# HPI_dice.net
KiCad netlist of a schematic drawn in EAGLE
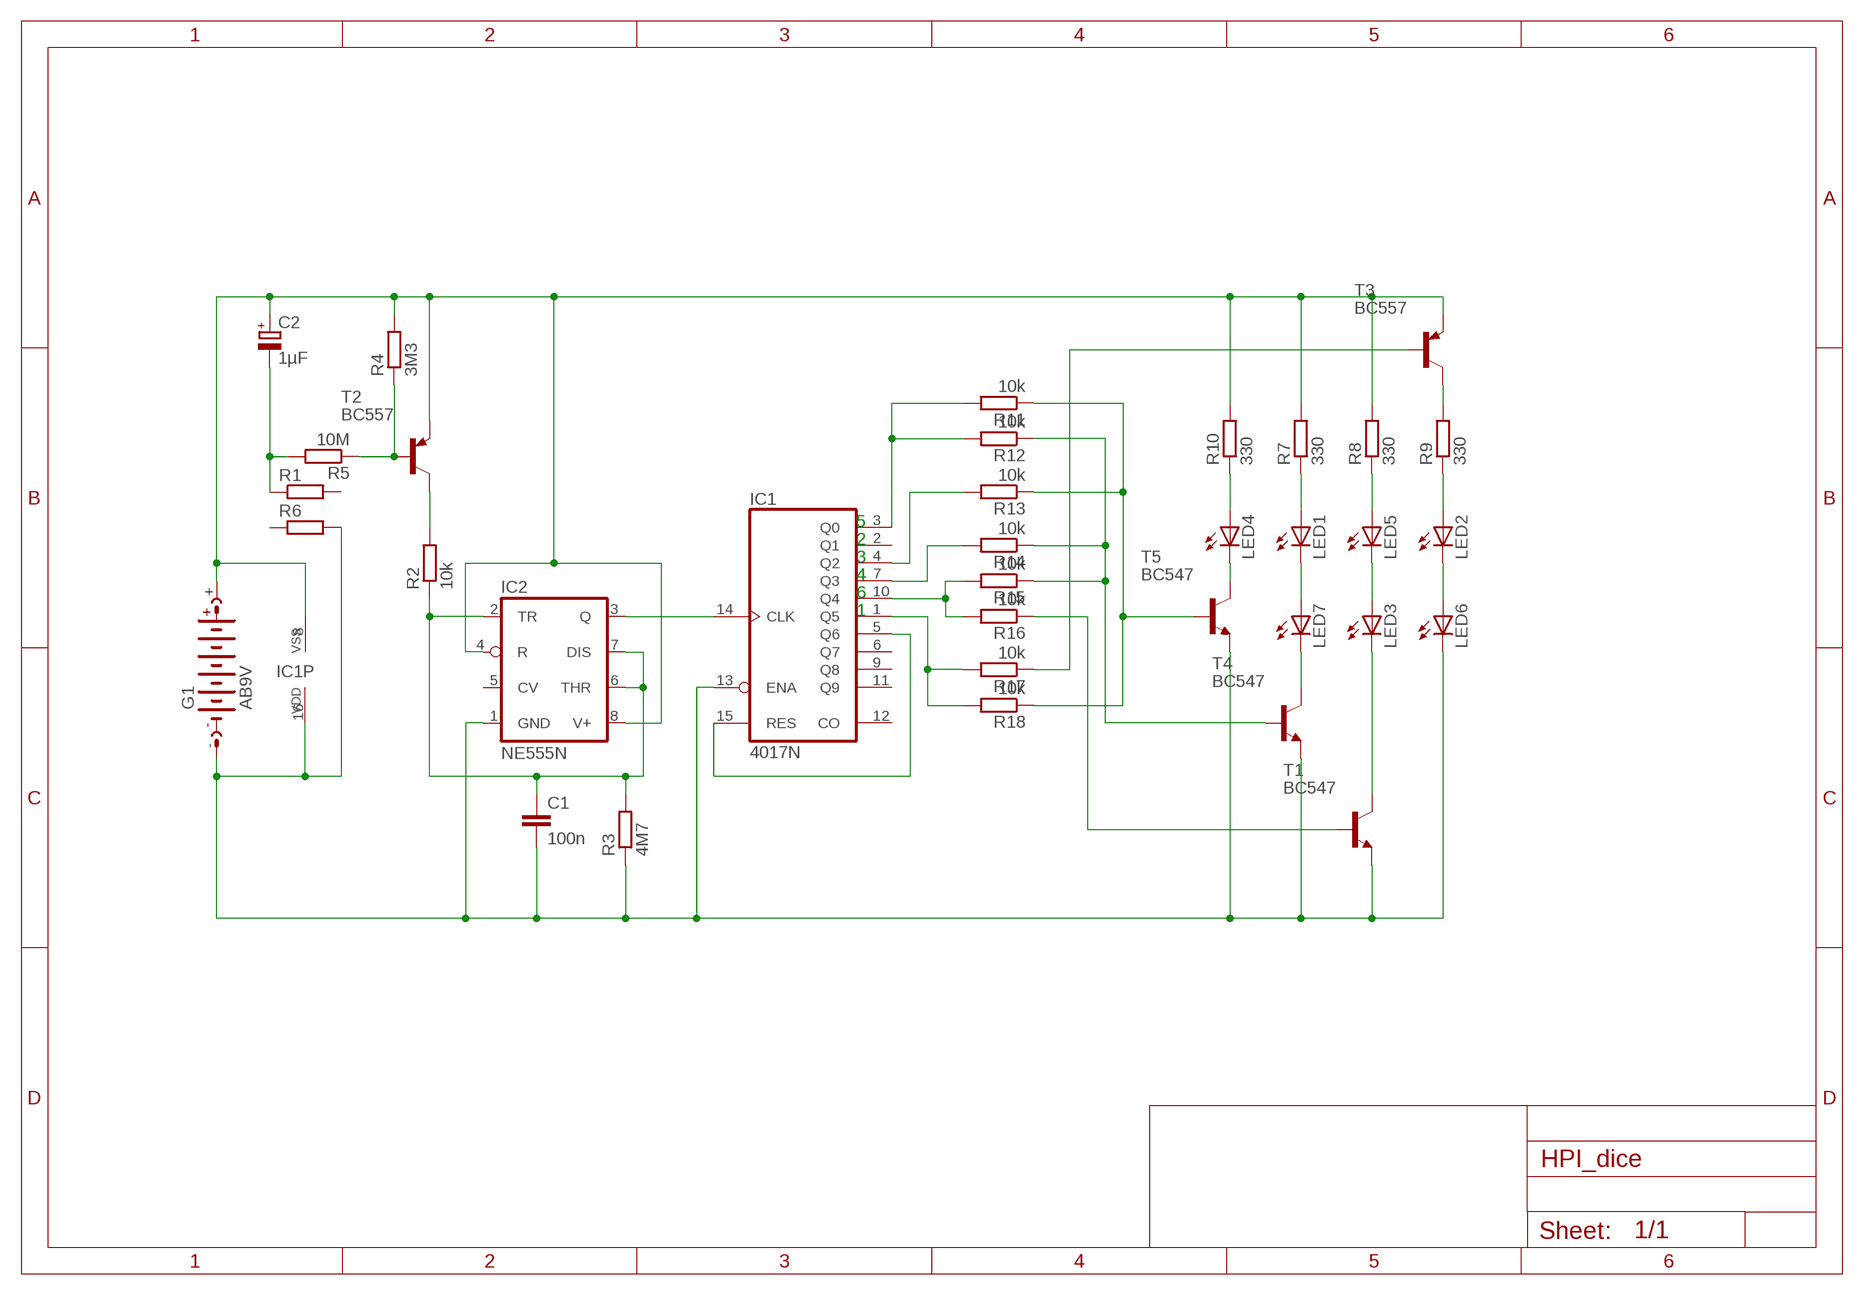
[diagram p0: schematic, sheet 1]

(export (version "E")
  (design (tool "Eeschema 10.0.6"))
  (components
    (comp (ref "C1")
      (value "100n")
      (footprint "eagle-import:C050-025X075")
      (libsource (lib "eagle-import") (part "C-EU050-025X075"))
    )
    (comp (ref "C2")
      (value "1µF")
      (footprint "eagle-import:E2,5-6")
      (libsource (lib "eagle-import") (part "CPOL-EUE2.5-6"))
    )
    (comp (ref "G1")
      (value "AB9V")
      (footprint "eagle-import:AB9V")
      (libsource (lib "eagle-import") (part "AB9V"))
    )
    (comp (ref "IC1")
      (value "4017N")
      (footprint "eagle-import:DIL16")
      (libsource (lib "eagle-import") (part "4017N"))
    )
    (comp (ref "IC2")
      (value "NE555N")
      (footprint "eagle-import:DIL08")
      (libsource (lib "eagle-import") (part "555NNE"))
    )
    (comp (ref "LED1")
      (value "LED3MM")
      (footprint "eagle-import:LED3MM")
      (libsource (lib "eagle-import") (part "LED3MM"))
    )
    (comp (ref "LED2")
      (value "LED3MM")
      (footprint "eagle-import:LED3MM")
      (libsource (lib "eagle-import") (part "LED3MM"))
    )
    (comp (ref "LED3")
      (value "LED3MM")
      (footprint "eagle-import:LED3MM")
      (libsource (lib "eagle-import") (part "LED3MM"))
    )
    (comp (ref "LED4")
      (value "LED3MM")
      (footprint "eagle-import:LED3MM")
      (libsource (lib "eagle-import") (part "LED3MM"))
    )
    (comp (ref "LED5")
      (value "LED3MM")
      (footprint "eagle-import:LED3MM")
      (libsource (lib "eagle-import") (part "LED3MM"))
    )
    (comp (ref "LED6")
      (value "LED3MM")
      (footprint "eagle-import:LED3MM")
      (libsource (lib "eagle-import") (part "LED3MM"))
    )
    (comp (ref "LED7")
      (value "LED3MM")
      (footprint "eagle-import:LED3MM")
      (libsource (lib "eagle-import") (part "LED3MM"))
    )
    (comp (ref "R1")
      (value "R-EU_0207/10")
      (footprint "eagle-import:0207_10")
      (libsource (lib "eagle-import") (part "R-EU_0207/10"))
    )
    (comp (ref "R2")
      (value "10k")
      (footprint "eagle-import:0207_10")
      (libsource (lib "eagle-import") (part "R-EU_0207/10"))
    )
    (comp (ref "R3")
      (value "4M7")
      (footprint "eagle-import:0207_10")
      (libsource (lib "eagle-import") (part "R-EU_0207/10"))
    )
    (comp (ref "R4")
      (value "3M3")
      (footprint "eagle-import:0207_10")
      (libsource (lib "eagle-import") (part "R-EU_0207/10"))
    )
    (comp (ref "R5")
      (value "10M")
      (footprint "eagle-import:0207_10")
      (libsource (lib "eagle-import") (part "R-EU_0207/10"))
    )
    (comp (ref "R6")
      (value "R-EU_0207/10")
      (footprint "eagle-import:0207_10")
      (libsource (lib "eagle-import") (part "R-EU_0207/10"))
    )
    (comp (ref "R7")
      (value "330")
      (footprint "eagle-import:0207_10")
      (libsource (lib "eagle-import") (part "R-EU_0207/10"))
    )
    (comp (ref "R8")
      (value "330")
      (footprint "eagle-import:0207_10")
      (libsource (lib "eagle-import") (part "R-EU_0207/10"))
    )
    (comp (ref "R9")
      (value "330")
      (footprint "eagle-import:0207_10")
      (libsource (lib "eagle-import") (part "R-EU_0207/10"))
    )
    (comp (ref "R10")
      (value "330")
      (footprint "eagle-import:0207_10")
      (libsource (lib "eagle-import") (part "R-EU_0207/10"))
    )
    (comp (ref "R11")
      (value "10k")
      (footprint "eagle-import:0207_10")
      (libsource (lib "eagle-import") (part "R-EU_0207/10"))
    )
    (comp (ref "R12")
      (value "10k")
      (footprint "eagle-import:0207_10")
      (libsource (lib "eagle-import") (part "R-EU_0207/10"))
    )
    (comp (ref "R13")
      (value "10k")
      (footprint "eagle-import:0207_10")
      (libsource (lib "eagle-import") (part "R-EU_0207/10"))
    )
    (comp (ref "R14")
      (value "10k")
      (footprint "eagle-import:0207_10")
      (libsource (lib "eagle-import") (part "R-EU_0207/10"))
    )
    (comp (ref "R15")
      (value "10k")
      (footprint "eagle-import:0207_10")
      (libsource (lib "eagle-import") (part "R-EU_0207/10"))
    )
    (comp (ref "R16")
      (value "10k")
      (footprint "eagle-import:0207_10")
      (libsource (lib "eagle-import") (part "R-EU_0207/10"))
    )
    (comp (ref "R17")
      (value "10k")
      (footprint "eagle-import:0207_10")
      (libsource (lib "eagle-import") (part "R-EU_0207/10"))
    )
    (comp (ref "R18")
      (value "10k")
      (footprint "eagle-import:0207_10")
      (libsource (lib "eagle-import") (part "R-EU_0207/10"))
    )
    (comp (ref "T1")
      (value "BC547")
      (footprint "eagle-import:TO92")
      (libsource (lib "eagle-import") (part "BC547"))
    )
    (comp (ref "T2")
      (value "BC557")
      (footprint "eagle-import:TO92")
      (libsource (lib "eagle-import") (part "BC557"))
    )
    (comp (ref "T3")
      (value "BC557")
      (footprint "eagle-import:TO92")
      (libsource (lib "eagle-import") (part "BC557"))
    )
    (comp (ref "T4")
      (value "BC547")
      (footprint "eagle-import:TO92")
      (libsource (lib "eagle-import") (part "BC547"))
    )
    (comp (ref "T5")
      (value "BC547")
      (footprint "eagle-import:TO92")
      (libsource (lib "eagle-import") (part "BC547"))
    )
  )
  (nets
    (net (code "1") (name "Net-(C2-Pad-)") (class "Default")
      (node (ref "C2") (pin "-") (pinfunction "-_-") (pintype "passive"))
      (node (ref "R1") (pin "1") (pinfunction "1_1") (pintype "passive"))
      (node (ref "R5") (pin "2") (pinfunction "2_2") (pintype "passive"))
    )
    (net (code "2") (name "Net-(IC1A-CLK)") (class "Default")
      (node (ref "IC1") (pin "14") (pinfunction "CLK_14") (pintype "input"))
      (node (ref "IC2") (pin "3") (pinfunction "Q_3") (pintype "output"))
    )
    (net (code "3") (name "Net-(IC1A-ENA)") (class "Default")
      (node (ref "C1") (pin "2") (pinfunction "2_2") (pintype "passive"))
      (node (ref "G1") (pin "-") (pinfunction "-_-") (pintype "passive"))
      (node (ref "IC1") (pin "13") (pinfunction "ENA_13") (pintype "input"))
      (node (ref "IC1") (pin "16") (pinfunction "VDD_16") (pintype "power_in"))
      (node (ref "IC2") (pin "1") (pinfunction "GND_1") (pintype "power_in"))
      (node (ref "LED6") (pin "K") (pinfunction "C_K") (pintype "passive"))
      (node (ref "R3") (pin "1") (pinfunction "1_1") (pintype "passive"))
      (node (ref "R6") (pin "2") (pinfunction "2_2") (pintype "passive"))
      (node (ref "T1") (pin "1") (pinfunction "E_1") (pintype "passive"))
      (node (ref "T4") (pin "1") (pinfunction "E_1") (pintype "passive"))
      (node (ref "T5") (pin "1") (pinfunction "E_1") (pintype "passive"))
    )
    (net (code "4") (name "Net-(IC1A-Q0)") (class "Default")
      (node (ref "IC1") (pin "3") (pinfunction "Q0_3") (pintype "output"))
      (node (ref "R11") (pin "2") (pinfunction "2_2") (pintype "passive"))
      (node (ref "R12") (pin "2") (pinfunction "2_2") (pintype "passive"))
    )
    (net (code "5") (name "Net-(IC1A-Q2)") (class "Default")
      (node (ref "IC1") (pin "4") (pinfunction "Q2_4") (pintype "output"))
      (node (ref "R13") (pin "2") (pinfunction "2_2") (pintype "passive"))
    )
    (net (code "6") (name "Net-(IC1A-Q3)") (class "Default")
      (node (ref "IC1") (pin "7") (pinfunction "Q3_7") (pintype "output"))
      (node (ref "R14") (pin "2") (pinfunction "2_2") (pintype "passive"))
    )
    (net (code "7") (name "Net-(IC1A-Q4)") (class "Default")
      (node (ref "IC1") (pin "10") (pinfunction "Q4_10") (pintype "output"))
      (node (ref "R15") (pin "2") (pinfunction "2_2") (pintype "passive"))
      (node (ref "R16") (pin "2") (pinfunction "2_2") (pintype "passive"))
    )
    (net (code "8") (name "Net-(IC1A-Q5)") (class "Default")
      (node (ref "IC1") (pin "1") (pinfunction "Q5_1") (pintype "output"))
      (node (ref "R17") (pin "2") (pinfunction "2_2") (pintype "passive"))
      (node (ref "R18") (pin "2") (pinfunction "2_2") (pintype "passive"))
    )
    (net (code "9") (name "Net-(IC1A-Q6)") (class "Default")
      (node (ref "IC1") (pin "15") (pinfunction "RES_15") (pintype "input"))
      (node (ref "IC1") (pin "5") (pinfunction "Q6_5") (pintype "output"))
    )
    (net (code "10") (name "Net-(IC1B-VSS)") (class "Default")
      (node (ref "C2") (pin "+") (pinfunction "+_+") (pintype "passive"))
      (node (ref "G1") (pin "+") (pinfunction "+_+") (pintype "passive"))
      (node (ref "IC1") (pin "8") (pinfunction "VSS_8") (pintype "power_in"))
      (node (ref "IC2") (pin "4") (pinfunction "R_4") (pintype "input"))
      (node (ref "IC2") (pin "8") (pinfunction "V+_8") (pintype "power_in"))
      (node (ref "R10") (pin "2") (pinfunction "2_2") (pintype "passive"))
      (node (ref "R4") (pin "2") (pinfunction "2_2") (pintype "passive"))
      (node (ref "R7") (pin "2") (pinfunction "2_2") (pintype "passive"))
      (node (ref "R8") (pin "2") (pinfunction "2_2") (pintype "passive"))
      (node (ref "T2") (pin "1") (pinfunction "E_1") (pintype "passive"))
      (node (ref "T3") (pin "1") (pinfunction "E_1") (pintype "passive"))
    )
    (net (code "11") (name "Net-(IC2-DIS)") (class "Default")
      (node (ref "C1") (pin "1") (pinfunction "1_1") (pintype "passive"))
      (node (ref "IC2") (pin "2") (pinfunction "TR_2") (pintype "input"))
      (node (ref "IC2") (pin "6") (pinfunction "THR_6") (pintype "input"))
      (node (ref "IC2") (pin "7") (pinfunction "DIS_7") (pintype "input"))
      (node (ref "R2") (pin "1") (pinfunction "1_1") (pintype "passive"))
      (node (ref "R3") (pin "2") (pinfunction "2_2") (pintype "passive"))
    )
    (net (code "12") (name "Net-(LED1-C)") (class "Default")
      (node (ref "LED1") (pin "K") (pinfunction "C_K") (pintype "passive"))
      (node (ref "LED7") (pin "A") (pinfunction "A_A") (pintype "passive"))
    )
    (net (code "13") (name "Net-(LED1-PadA)") (class "Default")
      (node (ref "LED1") (pin "A") (pinfunction "A_A") (pintype "passive"))
      (node (ref "R7") (pin "1") (pinfunction "1_1") (pintype "passive"))
    )
    (net (code "14") (name "Net-(LED2-C)") (class "Default")
      (node (ref "LED2") (pin "K") (pinfunction "C_K") (pintype "passive"))
      (node (ref "LED6") (pin "A") (pinfunction "A_A") (pintype "passive"))
    )
    (net (code "15") (name "Net-(LED2-PadA)") (class "Default")
      (node (ref "LED2") (pin "A") (pinfunction "A_A") (pintype "passive"))
      (node (ref "R9") (pin "1") (pinfunction "1_1") (pintype "passive"))
    )
    (net (code "16") (name "Net-(LED3-C)") (class "Default")
      (node (ref "LED3") (pin "K") (pinfunction "C_K") (pintype "passive"))
      (node (ref "T1") (pin "3") (pinfunction "C_3") (pintype "passive"))
    )
    (net (code "17") (name "Net-(LED4-C)") (class "Default")
      (node (ref "LED4") (pin "K") (pinfunction "C_K") (pintype "passive"))
      (node (ref "T5") (pin "3") (pinfunction "C_3") (pintype "passive"))
    )
    (net (code "18") (name "Net-(LED4-PadA)") (class "Default")
      (node (ref "LED4") (pin "A") (pinfunction "A_A") (pintype "passive"))
      (node (ref "R10") (pin "1") (pinfunction "1_1") (pintype "passive"))
    )
    (net (code "19") (name "Net-(LED5-C)") (class "Default")
      (node (ref "LED3") (pin "A") (pinfunction "A_A") (pintype "passive"))
      (node (ref "LED5") (pin "K") (pinfunction "C_K") (pintype "passive"))
    )
    (net (code "20") (name "Net-(LED5-PadA)") (class "Default")
      (node (ref "LED5") (pin "A") (pinfunction "A_A") (pintype "passive"))
      (node (ref "R8") (pin "1") (pinfunction "1_1") (pintype "passive"))
    )
    (net (code "21") (name "Net-(LED7-C)") (class "Default")
      (node (ref "LED7") (pin "K") (pinfunction "C_K") (pintype "passive"))
      (node (ref "T4") (pin "3") (pinfunction "C_3") (pintype "passive"))
    )
    (net (code "22") (name "Net-(T1-B)") (class "Default")
      (node (ref "R16") (pin "1") (pinfunction "1_1") (pintype "passive"))
      (node (ref "T1") (pin "2") (pinfunction "B_2") (pintype "passive"))
    )
    (net (code "23") (name "Net-(T2-B)") (class "Default")
      (node (ref "R4") (pin "1") (pinfunction "1_1") (pintype "passive"))
      (node (ref "R5") (pin "1") (pinfunction "1_1") (pintype "passive"))
      (node (ref "T2") (pin "2") (pinfunction "B_2") (pintype "passive"))
    )
    (net (code "24") (name "Net-(T2-C)") (class "Default")
      (node (ref "R2") (pin "2") (pinfunction "2_2") (pintype "passive"))
      (node (ref "T2") (pin "3") (pinfunction "C_3") (pintype "passive"))
    )
    (net (code "25") (name "Net-(T3-B)") (class "Default")
      (node (ref "R17") (pin "1") (pinfunction "1_1") (pintype "passive"))
      (node (ref "T3") (pin "2") (pinfunction "B_2") (pintype "passive"))
    )
    (net (code "26") (name "Net-(T3-C)") (class "Default")
      (node (ref "R9") (pin "2") (pinfunction "2_2") (pintype "passive"))
      (node (ref "T3") (pin "3") (pinfunction "C_3") (pintype "passive"))
    )
    (net (code "27") (name "Net-(T4-B)") (class "Default")
      (node (ref "R12") (pin "1") (pinfunction "1_1") (pintype "passive"))
      (node (ref "R14") (pin "1") (pinfunction "1_1") (pintype "passive"))
      (node (ref "R15") (pin "1") (pinfunction "1_1") (pintype "passive"))
      (node (ref "T4") (pin "2") (pinfunction "B_2") (pintype "passive"))
    )
    (net (code "28") (name "Net-(T5-B)") (class "Default")
      (node (ref "R11") (pin "1") (pinfunction "1_1") (pintype "passive"))
      (node (ref "R13") (pin "1") (pinfunction "1_1") (pintype "passive"))
      (node (ref "R18") (pin "1") (pinfunction "1_1") (pintype "passive"))
      (node (ref "T5") (pin "2") (pinfunction "B_2") (pintype "passive"))
    )
    (net (code "29") (name "unconnected-(IC1A-CO-Pad12)") (class "Default")
      (node (ref "IC1") (pin "12") (pinfunction "CO_12") (pintype "output"))
    )
    (net (code "30") (name "unconnected-(IC1A-Q1-Pad2)") (class "Default")
      (node (ref "IC1") (pin "2") (pinfunction "Q1_2") (pintype "output"))
    )
    (net (code "31") (name "unconnected-(IC1A-Q7-Pad6)") (class "Default")
      (node (ref "IC1") (pin "6") (pinfunction "Q7_6") (pintype "output"))
    )
    (net (code "32") (name "unconnected-(IC1A-Q8-Pad9)") (class "Default")
      (node (ref "IC1") (pin "9") (pinfunction "Q8_9") (pintype "output"))
    )
    (net (code "33") (name "unconnected-(IC1A-Q9-Pad11)") (class "Default")
      (node (ref "IC1") (pin "11") (pinfunction "Q9_11") (pintype "output"))
    )
    (net (code "34") (name "unconnected-(IC2-CV-Pad5)") (class "Default")
      (node (ref "IC2") (pin "5") (pinfunction "CV_5") (pintype "input"))
    )
    (net (code "35") (name "unconnected-(R1-Pad2)") (class "Default")
      (node (ref "R1") (pin "2") (pinfunction "2_2") (pintype "passive"))
    )
    (net (code "36") (name "unconnected-(R6-Pad1)") (class "Default")
      (node (ref "R6") (pin "1") (pinfunction "1_1") (pintype "passive"))
    )
  )
)
